# SCH_Tiny_printer_small_2024-11-19.net
KiCad netlist of a schematic drawn in EasyEDA
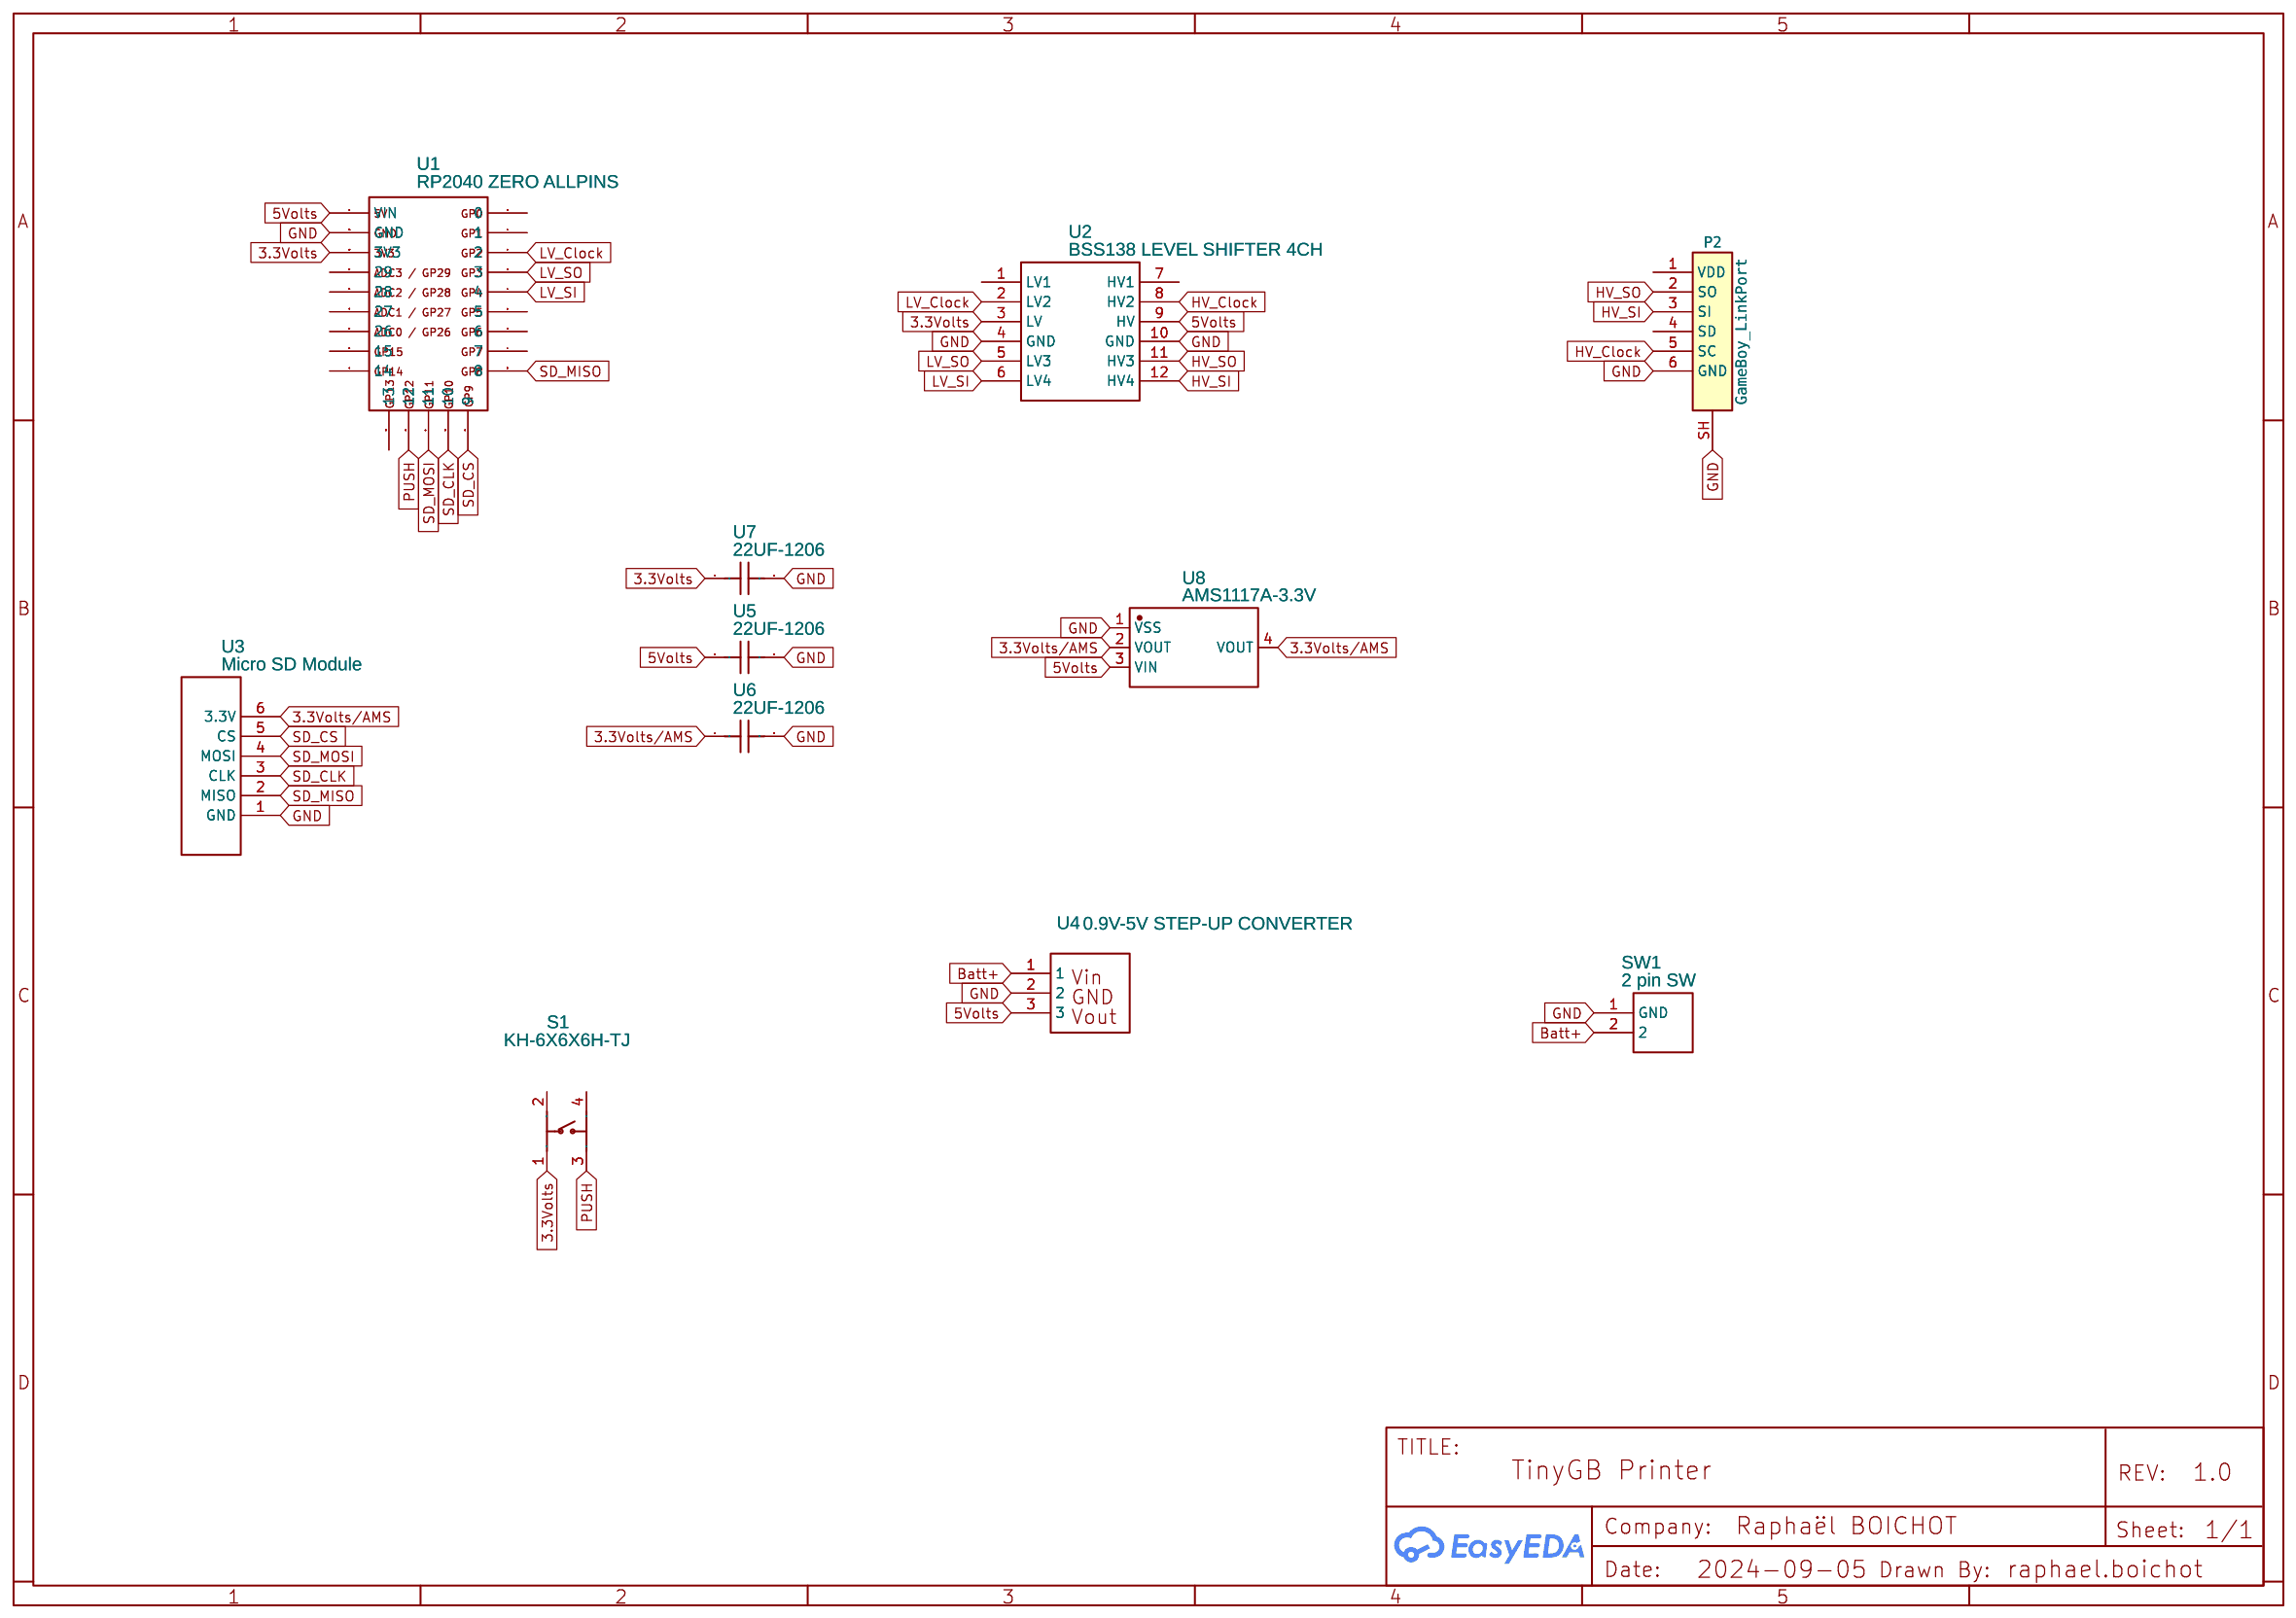
[diagram p0: schematic sheet]

(export (version "E")
  (design (tool "Eeschema 10.0.6"))
  (components
    (comp (ref "P2") (value "GameBoy_LinkPort") (libsource (lib "") (part "Unknown_860_-645")))
    (comp (ref "S1")
      (value "KH-6X6X6H-TJ")
      (fields (field (name "Manufacturer") "kinghelm(金航标)"))
      (libsource (lib "") (part "KH-6X6X6H-TJ"))
    )
    (comp (ref "SW1")
      (value "2 pin SW")
      (fields (field (name "Manufacturer") "NA"))
      (libsource (lib "") (part "2 pin SW"))
    )
    (comp (ref "U1")
      (value "RP2040 ZERO ALLPINS")
      (fields (field (name "Manufacturer Part") "RP2040 Zero") (field (name "Manufacturer") "Waveshare"))
      (libsource (lib "") (part "RP2040 ZERO ALLPINS"))
    )
    (comp (ref "U2")
      (value "BSS138 LEVEL SHIFTER 4CH")
      (fields (field (name "Manufacturer Part") "BSS138") (field (name "Manufacturer") "ON Semiconductor"))
      (libsource (lib "") (part "BSS138 LEVEL SHIFTER 4CH"))
    )
    (comp (ref "U3") (value "Micro SD Module") (libsource (lib "") (part "Micro SD Module")))
    (comp (ref "U4")
      (value "0.9V-5V STEP-UP CONVERTER")
      (fields (field (name "Manufacturer") "Generic"))
      (libsource (lib "") (part "0.9V-5V STEP-UP CONVERTER"))
    )
    (comp (ref "U5")
      (value "22UF-1206")
      (fields (field (name "Manufacturer Part") "220UF-1206"))
      (libsource (lib "") (part "220UF-1206"))
    )
    (comp (ref "U6")
      (value "22UF-1206")
      (fields (field (name "Manufacturer Part") "220UF-1206"))
      (libsource (lib "") (part "220UF-1206"))
    )
    (comp (ref "U7")
      (value "22UF-1206")
      (fields (field (name "Manufacturer Part") "220UF-1206"))
      (libsource (lib "") (part "220UF-1206"))
    )
    (comp (ref "U8")
      (value "AMS1117A-3.3V")
      (fields (field (name "Manufacturer") "HX(恒佳兴)"))
      (libsource (lib "") (part "AMS1117A-3.3V"))
    )
  )
  (nets
    (net (code "1") (name "3.3Volts") (class "Default")
      (node (ref "S1") (pin "1") (pinfunction "1_1") (pintype "unspecified"))
      (node (ref "U1") (pin "3V3") (pinfunction "3V3_3V3") (pintype "unspecified"))
      (node (ref "U2") (pin "3") (pinfunction "LV_3") (pintype "passive"))
      (node (ref "U7") (pin "1") (pinfunction "1_1") (pintype "unspecified"))
    )
    (net (code "2") (name "3.3Volts{slash}AMS") (class "Default")
      (node (ref "U3") (pin "6") (pinfunction "3.3V_6") (pintype "unspecified"))
      (node (ref "U6") (pin "1") (pinfunction "1_1") (pintype "unspecified"))
      (node (ref "U8") (pin "2") (pinfunction "VOUT_2") (pintype "unspecified"))
      (node (ref "U8") (pin "4") (pinfunction "VOUT_4") (pintype "unspecified"))
    )
    (net (code "3") (name "5Volts") (class "Default")
      (node (ref "U1") (pin "VIN") (pinfunction "VIN_VIN") (pintype "unspecified"))
      (node (ref "U2") (pin "9") (pinfunction "HV_9") (pintype "passive"))
      (node (ref "U4") (pin "3") (pinfunction "3_3") (pintype "unspecified"))
      (node (ref "U5") (pin "1") (pinfunction "1_1") (pintype "unspecified"))
      (node (ref "U8") (pin "3") (pinfunction "VIN_3") (pintype "unspecified"))
    )
    (net (code "4") (name "Batt+") (class "Default")
      (node (ref "SW1") (pin "2") (pinfunction "2_2") (pintype "unspecified"))
      (node (ref "U4") (pin "1") (pinfunction "1_1") (pintype "unspecified"))
    )
    (net (code "5") (name "GND") (class "Default")
      (node (ref "P2") (pin "6") (pinfunction "GND_6") (pintype "unspecified"))
      (node (ref "P2") (pin "SH") (pintype "unspecified"))
      (node (ref "SW1") (pin "1") (pinfunction "GND_1") (pintype "unspecified"))
      (node (ref "U1") (pin "GND") (pinfunction "GND_GND") (pintype "unspecified"))
      (node (ref "U2") (pin "10") (pinfunction "GND_10") (pintype "passive"))
      (node (ref "U2") (pin "4") (pinfunction "GND_4") (pintype "passive"))
      (node (ref "U3") (pin "1") (pinfunction "GND_1") (pintype "unspecified"))
      (node (ref "U4") (pin "2") (pinfunction "2_2") (pintype "unspecified"))
      (node (ref "U5") (pin "2") (pinfunction "2_2") (pintype "unspecified"))
      (node (ref "U6") (pin "2") (pinfunction "2_2") (pintype "unspecified"))
      (node (ref "U7") (pin "2") (pinfunction "2_2") (pintype "unspecified"))
      (node (ref "U8") (pin "1") (pinfunction "VSS_1") (pintype "unspecified"))
    )
    (net (code "6") (name "HV_Clock") (class "Default")
      (node (ref "P2") (pin "5") (pinfunction "SC_5") (pintype "unspecified"))
      (node (ref "U2") (pin "8") (pinfunction "HV2_8") (pintype "output"))
    )
    (net (code "7") (name "HV_SI") (class "Default")
      (node (ref "P2") (pin "3") (pinfunction "SI_3") (pintype "unspecified"))
      (node (ref "U2") (pin "12") (pinfunction "HV4_12") (pintype "output"))
    )
    (net (code "8") (name "HV_SO") (class "Default")
      (node (ref "P2") (pin "2") (pinfunction "SO_2") (pintype "unspecified"))
      (node (ref "U2") (pin "11") (pinfunction "HV3_11") (pintype "output"))
    )
    (net (code "9") (name "LV_Clock") (class "Default")
      (node (ref "U1") (pin "2") (pinfunction "2_2") (pintype "unspecified"))
      (node (ref "U2") (pin "2") (pinfunction "LV2_2") (pintype "input"))
    )
    (net (code "10") (name "LV_SI") (class "Default")
      (node (ref "U1") (pin "4") (pinfunction "4_4") (pintype "unspecified"))
      (node (ref "U2") (pin "6") (pinfunction "LV4_6") (pintype "input"))
    )
    (net (code "11") (name "LV_SO") (class "Default")
      (node (ref "U1") (pin "3") (pinfunction "3_3") (pintype "unspecified"))
      (node (ref "U2") (pin "5") (pinfunction "LV3_5") (pintype "input"))
    )
    (net (code "12") (name "PUSH") (class "Default")
      (node (ref "S1") (pin "3") (pinfunction "3_3") (pintype "unspecified"))
      (node (ref "U1") (pin "12") (pinfunction "12_12") (pintype "unspecified"))
    )
    (net (code "13") (name "SD_CLK") (class "Default")
      (node (ref "U1") (pin "10") (pinfunction "10_10") (pintype "unspecified"))
      (node (ref "U3") (pin "3") (pinfunction "CLK_3") (pintype "unspecified"))
    )
    (net (code "14") (name "SD_CS") (class "Default")
      (node (ref "U1") (pin "9") (pinfunction "9_9") (pintype "unspecified"))
      (node (ref "U3") (pin "5") (pinfunction "CS_5") (pintype "unspecified"))
    )
    (net (code "15") (name "SD_MISO") (class "Default")
      (node (ref "U1") (pin "8") (pinfunction "8_8") (pintype "unspecified"))
      (node (ref "U3") (pin "2") (pinfunction "MISO_2") (pintype "unspecified"))
    )
    (net (code "16") (name "SD_MOSI") (class "Default")
      (node (ref "U1") (pin "11") (pinfunction "11_11") (pintype "unspecified"))
      (node (ref "U3") (pin "4") (pinfunction "MOSI_4") (pintype "unspecified"))
    )
    (net (code "17") (name "unconnected-(P2-SD-Pad4)") (class "Default")
      (node (ref "P2") (pin "4") (pinfunction "SD_4") (pintype "unspecified"))
    )
    (net (code "18") (name "unconnected-(P2-VDD-Pad1)") (class "Default")
      (node (ref "P2") (pin "1") (pinfunction "VDD_1") (pintype "unspecified"))
    )
    (net (code "19") (name "unconnected-(S1-Pad2)") (class "Default")
      (node (ref "S1") (pin "2") (pinfunction "2_2") (pintype "unspecified"))
    )
    (net (code "20") (name "unconnected-(S1-Pad4)") (class "Default")
      (node (ref "S1") (pin "4") (pinfunction "4_4") (pintype "unspecified"))
    )
    (net (code "21") (name "unconnected-(U1-Pad0)") (class "Default")
      (node (ref "U1") (pin "0") (pinfunction "0_0") (pintype "unspecified"))
    )
    (net (code "22") (name "unconnected-(U1-Pad1)") (class "Default")
      (node (ref "U1") (pin "1") (pinfunction "1_1") (pintype "unspecified"))
    )
    (net (code "23") (name "unconnected-(U1-Pad5)") (class "Default")
      (node (ref "U1") (pin "5") (pinfunction "5_5") (pintype "unspecified"))
    )
    (net (code "24") (name "unconnected-(U1-Pad6)") (class "Default")
      (node (ref "U1") (pin "6") (pinfunction "6_6") (pintype "unspecified"))
    )
    (net (code "25") (name "unconnected-(U1-Pad7)") (class "Default")
      (node (ref "U1") (pin "7") (pinfunction "7_7") (pintype "unspecified"))
    )
    (net (code "26") (name "unconnected-(U1-Pad13)") (class "Default")
      (node (ref "U1") (pin "13") (pinfunction "13_13") (pintype "unspecified"))
    )
    (net (code "27") (name "unconnected-(U1-Pad14)") (class "Default")
      (node (ref "U1") (pin "14") (pinfunction "14_14") (pintype "unspecified"))
    )
    (net (code "28") (name "unconnected-(U1-Pad15)") (class "Default")
      (node (ref "U1") (pin "15") (pinfunction "15_15") (pintype "unspecified"))
    )
    (net (code "29") (name "unconnected-(U1-Pad26)") (class "Default")
      (node (ref "U1") (pin "26") (pinfunction "26_26") (pintype "unspecified"))
    )
    (net (code "30") (name "unconnected-(U1-Pad27)") (class "Default")
      (node (ref "U1") (pin "27") (pinfunction "27_27") (pintype "unspecified"))
    )
    (net (code "31") (name "unconnected-(U1-Pad28)") (class "Default")
      (node (ref "U1") (pin "28") (pinfunction "28_28") (pintype "unspecified"))
    )
    (net (code "32") (name "unconnected-(U1-Pad29)") (class "Default")
      (node (ref "U1") (pin "29") (pinfunction "29_29") (pintype "unspecified"))
    )
    (net (code "33") (name "unconnected-(U2-HV1-Pad7)") (class "Default")
      (node (ref "U2") (pin "7") (pinfunction "HV1_7") (pintype "output"))
    )
    (net (code "34") (name "unconnected-(U2-LV1-Pad1)") (class "Default")
      (node (ref "U2") (pin "1") (pinfunction "LV1_1") (pintype "input"))
    )
  )
)
